# Sparkfun_RS232.net
KiCad netlist of a schematic drawn in EAGLE
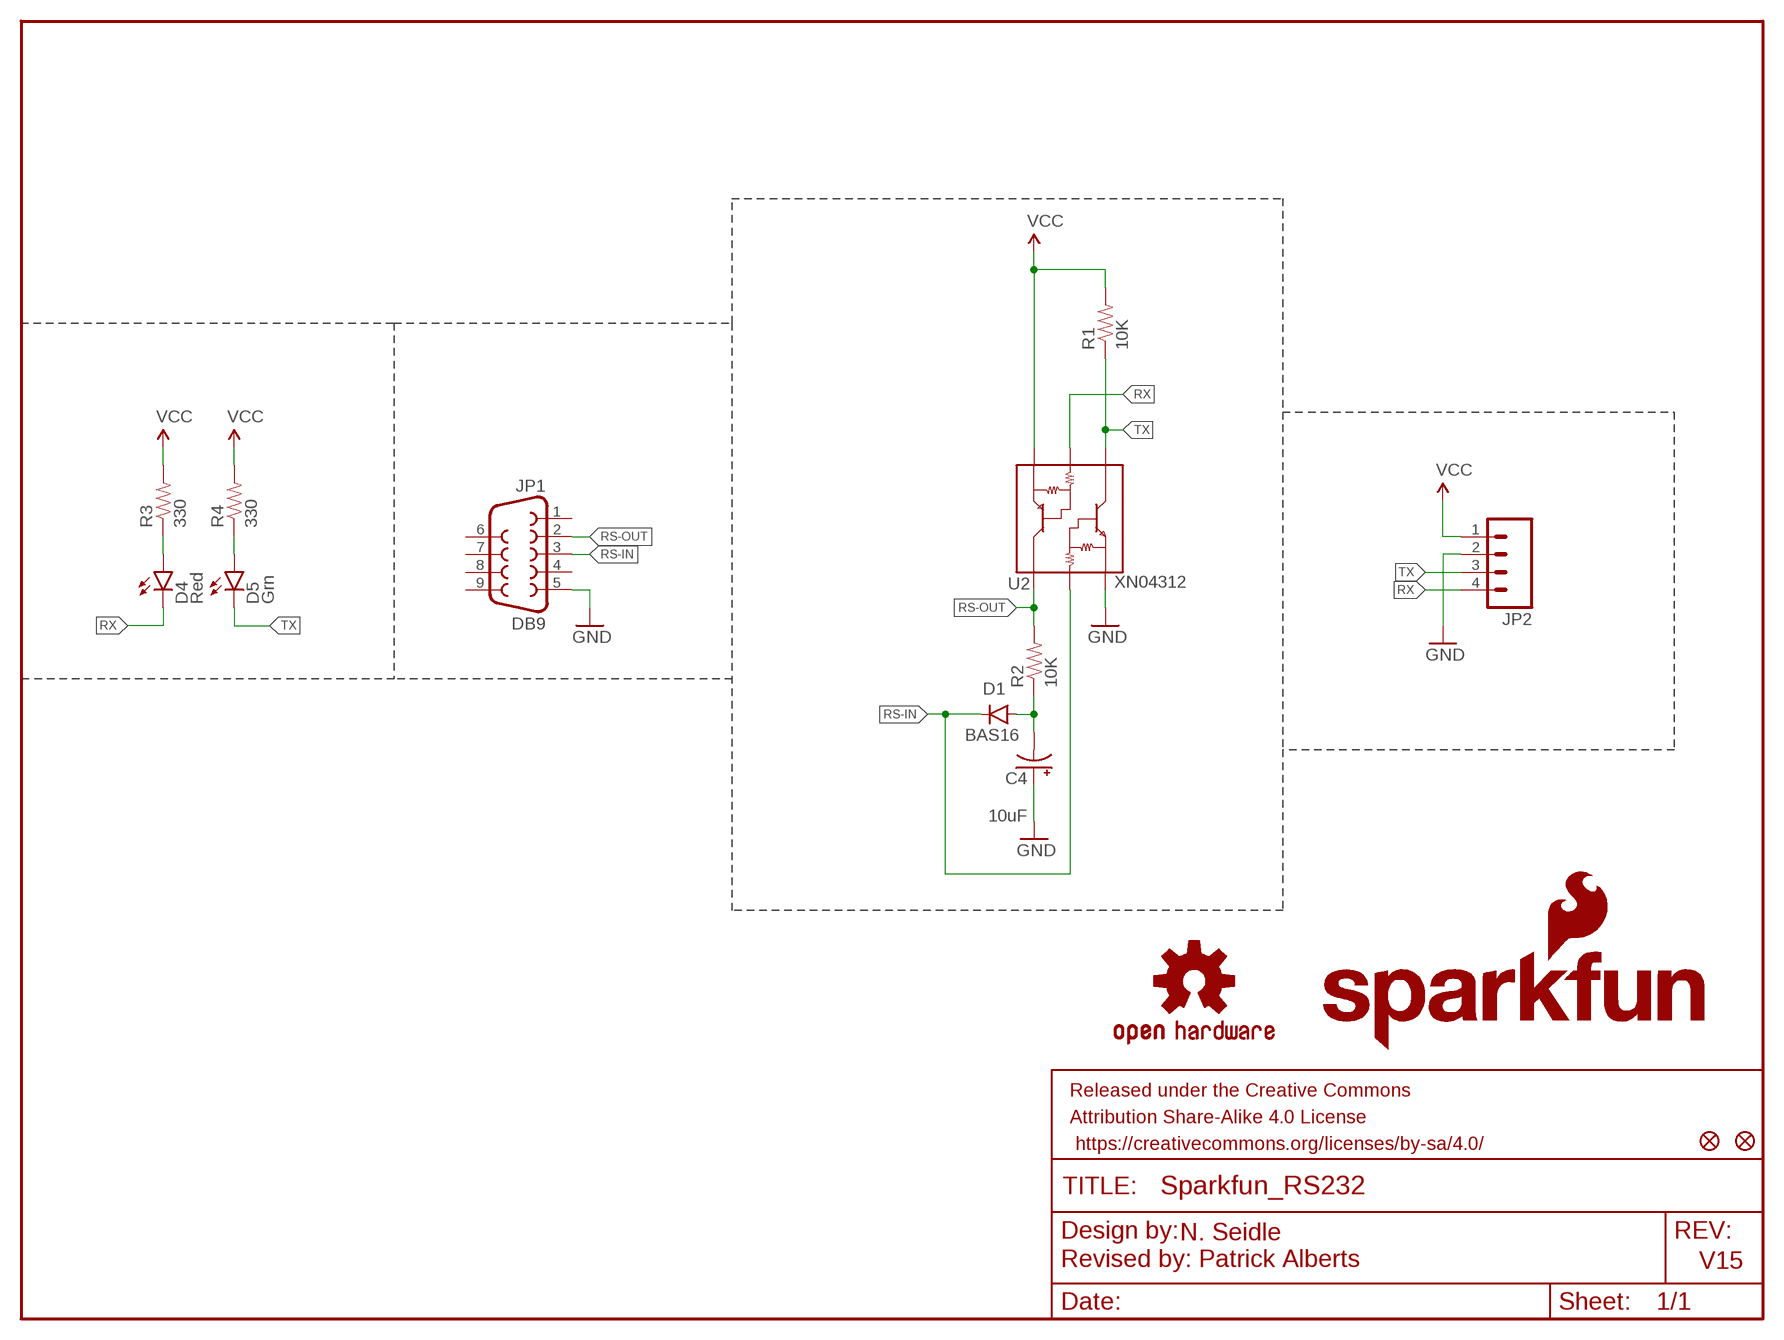
[diagram p0: schematic, sheet 1]

(export (version "E")
  (design (tool "Eeschema 10.0.6"))
  (components
    (comp (ref "C4")
      (value "10uF")
      (footprint "eagle-import:EIA3216")
      (libsource (lib "eagle-import") (part "10UF-16V-10%(TANT)"))
    )
    (comp (ref "D1")
      (value "BAS16")
      (footprint "eagle-import:SOD-323")
      (libsource (lib "eagle-import") (part "DIODEBAS16"))
    )
    (comp (ref "D4")
      (value "Red")
      (footprint "eagle-import:LED-1206")
      (libsource (lib "eagle-import") (part "LED-RED1206"))
    )
    (comp (ref "D5")
      (value "Grn")
      (footprint "eagle-import:LED-1206")
      (libsource (lib "eagle-import") (part "LED-GREENLARGE"))
    )
    (comp (ref "E$1")
      (value "FIDUCIAL1X2")
      (footprint "eagle-import:FIDUCIAL-1X2")
      (libsource (lib "eagle-import") (part "FIDUCIAL1X2"))
    )
    (comp (ref "E$2")
      (value "FIDUCIAL1X2")
      (footprint "eagle-import:FIDUCIAL-1X2")
      (libsource (lib "eagle-import") (part "FIDUCIAL1X2"))
    )
    (comp (ref "FRAME1")
      (value "FRAME-LETTER")
      (footprint "eagle-import:CREATIVE_COMMONS")
      (fields (field (name "DESIGNER") "NAME"))
      (libsource (lib "eagle-import") (part "FRAME-LETTER"))
    )
    (comp (ref "JP1")
      (value "DB9")
      (footprint "eagle-import:DB9")
      (libsource (lib "eagle-import") (part "DB9FEMALE"))
    )
    (comp (ref "JP2")
      (value "M04PTH")
      (footprint "eagle-import:1X04")
      (libsource (lib "eagle-import") (part "M04PTH"))
    )
    (comp (ref "LOGO1")
      (value "SFE_LOGO_NAME_FLAME.1_INCH")
      (footprint "eagle-import:SFE_LOGO_NAME_FLAME_.1")
      (libsource (lib "eagle-import") (part "SFE_LOGO_NAME_FLAME.1_INCH"))
    )
    (comp (ref "LOGO2")
      (value "OSHW-LOGOM")
      (footprint "eagle-import:OSHW-LOGO-M")
      (libsource (lib "eagle-import") (part "OSHW-LOGOM"))
    )
    (comp (ref "R1")
      (value "10K")
      (footprint "eagle-import:0603-RES")
      (libsource (lib "eagle-import") (part "10KOHM1/10W1%(0603)0603"))
    )
    (comp (ref "R2")
      (value "10K")
      (footprint "eagle-import:0603-RES")
      (libsource (lib "eagle-import") (part "10KOHM1/10W1%(0603)0603"))
    )
    (comp (ref "R3")
      (value "330")
      (footprint "eagle-import:0603-RES")
      (libsource (lib "eagle-import") (part "330OHM1/10W1%(0603)"))
    )
    (comp (ref "R4")
      (value "330")
      (footprint "eagle-import:0603-RES")
      (libsource (lib "eagle-import") (part "330OHM1/10W1%(0603)"))
    )
    (comp (ref "U2")
      (value "XN04312")
      (footprint "eagle-import:SOT23-6")
      (libsource (lib "eagle-import") (part "XN04312SOT"))
    )
  )
  (nets
    (net (code "1") (name "GND") (class "Default")
      (node (ref "C4") (pin "A") (pinfunction "+_A") (pintype "passive"))
      (node (ref "JP1") (pin "5") (pinfunction "5_5") (pintype "passive"))
      (node (ref "JP2") (pin "2") (pinfunction "2_2") (pintype "passive"))
      (node (ref "U2") (pin "6") (pinfunction "E1_6") (pintype "bidirectional"))
    )
    (net (code "2") (name "Net-(C4--)") (class "Default")
      (node (ref "C4") (pin "C") (pinfunction "-_C") (pintype "passive"))
      (node (ref "D1") (pin "A") (pinfunction "A_A") (pintype "passive"))
      (node (ref "R2") (pin "1") (pinfunction "1_1") (pintype "passive"))
    )
    (net (code "3") (name "Net-(D4-PadA)") (class "Default")
      (node (ref "D4") (pin "A") (pinfunction "A_A") (pintype "passive"))
      (node (ref "R3") (pin "1") (pinfunction "1_1") (pintype "passive"))
    )
    (net (code "4") (name "Net-(D5-PadA)") (class "Default")
      (node (ref "D5") (pin "A") (pinfunction "A_A") (pintype "passive"))
      (node (ref "R4") (pin "1") (pinfunction "1_1") (pintype "passive"))
    )
    (net (code "5") (name "RS-IN") (class "Default")
      (node (ref "D1") (pin "C") (pinfunction "C_C") (pintype "passive"))
      (node (ref "JP1") (pin "3") (pinfunction "3_3") (pintype "passive"))
      (node (ref "U2") (pin "5") (pinfunction "B1_5") (pintype "bidirectional"))
    )
    (net (code "6") (name "RS-OUT") (class "Default")
      (node (ref "JP1") (pin "2") (pinfunction "2_2") (pintype "passive"))
      (node (ref "R2") (pin "2") (pinfunction "2_2") (pintype "passive"))
      (node (ref "U2") (pin "4") (pinfunction "C2_4") (pintype "bidirectional"))
    )
    (net (code "7") (name "RX") (class "Default")
      (node (ref "D4") (pin "C") (pinfunction "C_C") (pintype "passive"))
      (node (ref "JP2") (pin "4") (pinfunction "4_4") (pintype "passive"))
      (node (ref "U2") (pin "2") (pinfunction "B2_2") (pintype "bidirectional"))
    )
    (net (code "8") (name "TX") (class "Default")
      (node (ref "D5") (pin "C") (pinfunction "C_C") (pintype "passive"))
      (node (ref "JP2") (pin "3") (pinfunction "3_3") (pintype "passive"))
      (node (ref "R1") (pin "1") (pinfunction "1_1") (pintype "passive"))
      (node (ref "U2") (pin "1") (pinfunction "C1_1") (pintype "bidirectional"))
    )
    (net (code "9") (name "VCC") (class "Default")
      (node (ref "JP2") (pin "1") (pinfunction "1_1") (pintype "passive"))
      (node (ref "R1") (pin "2") (pinfunction "2_2") (pintype "passive"))
      (node (ref "R3") (pin "2") (pinfunction "2_2") (pintype "passive"))
      (node (ref "R4") (pin "2") (pinfunction "2_2") (pintype "passive"))
      (node (ref "U2") (pin "3") (pinfunction "E2_3") (pintype "bidirectional"))
    )
    (net (code "10") (name "unconnected-(JP1-Pad1)") (class "Default")
      (node (ref "JP1") (pin "1") (pinfunction "1_1") (pintype "passive"))
    )
    (net (code "11") (name "unconnected-(JP1-Pad4)") (class "Default")
      (node (ref "JP1") (pin "4") (pinfunction "4_4") (pintype "passive"))
    )
    (net (code "12") (name "unconnected-(JP1-Pad6)") (class "Default")
      (node (ref "JP1") (pin "6") (pinfunction "6_6") (pintype "passive"))
    )
    (net (code "13") (name "unconnected-(JP1-Pad7)") (class "Default")
      (node (ref "JP1") (pin "7") (pinfunction "7_7") (pintype "passive"))
    )
    (net (code "14") (name "unconnected-(JP1-Pad8)") (class "Default")
      (node (ref "JP1") (pin "8") (pinfunction "8_8") (pintype "passive"))
    )
    (net (code "15") (name "unconnected-(JP1-Pad9)") (class "Default")
      (node (ref "JP1") (pin "9") (pinfunction "9_9") (pintype "passive"))
    )
  )
)
